# SO-16-TSSOP-16-Adapter.net
KiCad netlist of a schematic drawn in EAGLE
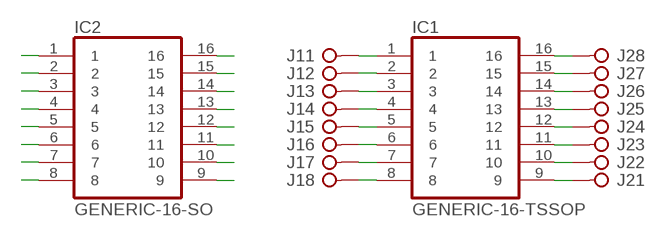
[diagram p0: schematic, sheet 1]

(export (version "E")
  (design (tool "Eeschema 10.0.6"))
  (components
    (comp (ref "IC1")
      (value "GENERIC-16-TSSOP")
      (footprint "eagle-import:TSSOP-16")
      (libsource (lib "eagle-import") (part "GENERIC-16-TSSOP"))
    )
    (comp (ref "IC2")
      (value "GENERIC-16-SO")
      (footprint "eagle-import:SO-16")
      (libsource (lib "eagle-import") (part "GENERIC-16-SO"))
    )
    (comp (ref "J1")
      (value "PINHD-1X8")
      (footprint "eagle-import:1X08")
      (libsource (lib "eagle-import") (part "PINHD-1X8"))
    )
    (comp (ref "J2")
      (value "PINHD-1X8")
      (footprint "eagle-import:1X08")
      (libsource (lib "eagle-import") (part "PINHD-1X8"))
    )
  )
  (nets
    (net (code "1") (name "/N$1") (class "Default")
      (node (ref "IC1") (pin "1") (pinfunction "1_1") (pintype "bidirectional"))
      (node (ref "IC2") (pin "16") (pinfunction "16_16") (pintype "bidirectional"))
      (node (ref "J1") (pin "1") (pinfunction "KL_1") (pintype "passive"))
    )
    (net (code "2") (name "/N$2") (class "Default")
      (node (ref "IC1") (pin "2") (pinfunction "2_2") (pintype "bidirectional"))
      (node (ref "IC2") (pin "15") (pinfunction "15_15") (pintype "bidirectional"))
      (node (ref "J1") (pin "2") (pinfunction "KL_2") (pintype "passive"))
    )
    (net (code "3") (name "/N$3") (class "Default")
      (node (ref "IC1") (pin "3") (pinfunction "3_3") (pintype "bidirectional"))
      (node (ref "IC2") (pin "14") (pinfunction "14_14") (pintype "bidirectional"))
      (node (ref "J1") (pin "3") (pinfunction "KL_3") (pintype "passive"))
    )
    (net (code "4") (name "/N$4") (class "Default")
      (node (ref "IC1") (pin "4") (pinfunction "4_4") (pintype "bidirectional"))
      (node (ref "IC2") (pin "13") (pinfunction "13_13") (pintype "bidirectional"))
      (node (ref "J1") (pin "4") (pinfunction "KL_4") (pintype "passive"))
    )
    (net (code "5") (name "/N$5") (class "Default")
      (node (ref "IC1") (pin "5") (pinfunction "5_5") (pintype "bidirectional"))
      (node (ref "IC2") (pin "12") (pinfunction "12_12") (pintype "bidirectional"))
      (node (ref "J1") (pin "5") (pinfunction "KL_5") (pintype "passive"))
    )
    (net (code "6") (name "/N$6") (class "Default")
      (node (ref "IC1") (pin "6") (pinfunction "6_6") (pintype "bidirectional"))
      (node (ref "IC2") (pin "11") (pinfunction "11_11") (pintype "bidirectional"))
      (node (ref "J1") (pin "6") (pinfunction "KL_6") (pintype "passive"))
    )
    (net (code "7") (name "/N$7") (class "Default")
      (node (ref "IC1") (pin "7") (pinfunction "7_7") (pintype "bidirectional"))
      (node (ref "IC2") (pin "10") (pinfunction "10_10") (pintype "bidirectional"))
      (node (ref "J1") (pin "7") (pinfunction "KL_7") (pintype "passive"))
    )
    (net (code "8") (name "/N$8") (class "Default")
      (node (ref "IC1") (pin "8") (pinfunction "8_8") (pintype "bidirectional"))
      (node (ref "IC2") (pin "9") (pinfunction "9_9") (pintype "bidirectional"))
      (node (ref "J1") (pin "8") (pinfunction "KL_8") (pintype "passive"))
    )
    (net (code "9") (name "/N$9") (class "Default")
      (node (ref "IC1") (pin "9") (pinfunction "9_9") (pintype "bidirectional"))
      (node (ref "IC2") (pin "8") (pinfunction "8_8") (pintype "bidirectional"))
      (node (ref "J2") (pin "1") (pinfunction "KL_1") (pintype "passive"))
    )
    (net (code "10") (name "/N$10") (class "Default")
      (node (ref "IC1") (pin "10") (pinfunction "10_10") (pintype "bidirectional"))
      (node (ref "IC2") (pin "7") (pinfunction "7_7") (pintype "bidirectional"))
      (node (ref "J2") (pin "2") (pinfunction "KL_2") (pintype "passive"))
    )
    (net (code "11") (name "/N$11") (class "Default")
      (node (ref "IC1") (pin "11") (pinfunction "11_11") (pintype "bidirectional"))
      (node (ref "IC2") (pin "6") (pinfunction "6_6") (pintype "bidirectional"))
      (node (ref "J2") (pin "3") (pinfunction "KL_3") (pintype "passive"))
    )
    (net (code "12") (name "/N$12") (class "Default")
      (node (ref "IC1") (pin "12") (pinfunction "12_12") (pintype "bidirectional"))
      (node (ref "IC2") (pin "5") (pinfunction "5_5") (pintype "bidirectional"))
      (node (ref "J2") (pin "4") (pinfunction "KL_4") (pintype "passive"))
    )
    (net (code "13") (name "/N$13") (class "Default")
      (node (ref "IC1") (pin "13") (pinfunction "13_13") (pintype "bidirectional"))
      (node (ref "IC2") (pin "4") (pinfunction "4_4") (pintype "bidirectional"))
      (node (ref "J2") (pin "5") (pinfunction "KL_5") (pintype "passive"))
    )
    (net (code "14") (name "/N$14") (class "Default")
      (node (ref "IC1") (pin "14") (pinfunction "14_14") (pintype "bidirectional"))
      (node (ref "IC2") (pin "3") (pinfunction "3_3") (pintype "bidirectional"))
      (node (ref "J2") (pin "6") (pinfunction "KL_6") (pintype "passive"))
    )
    (net (code "15") (name "/N$15") (class "Default")
      (node (ref "IC1") (pin "15") (pinfunction "15_15") (pintype "bidirectional"))
      (node (ref "IC2") (pin "2") (pinfunction "2_2") (pintype "bidirectional"))
      (node (ref "J2") (pin "7") (pinfunction "KL_7") (pintype "passive"))
    )
    (net (code "16") (name "/N$16") (class "Default")
      (node (ref "IC1") (pin "16") (pinfunction "16_16") (pintype "bidirectional"))
      (node (ref "IC2") (pin "1") (pinfunction "1_1") (pintype "bidirectional"))
      (node (ref "J2") (pin "8") (pinfunction "KL_8") (pintype "passive"))
    )
  )
)
